# anemometer-r2.net
KiCad netlist of a schematic drawn in EAGLE
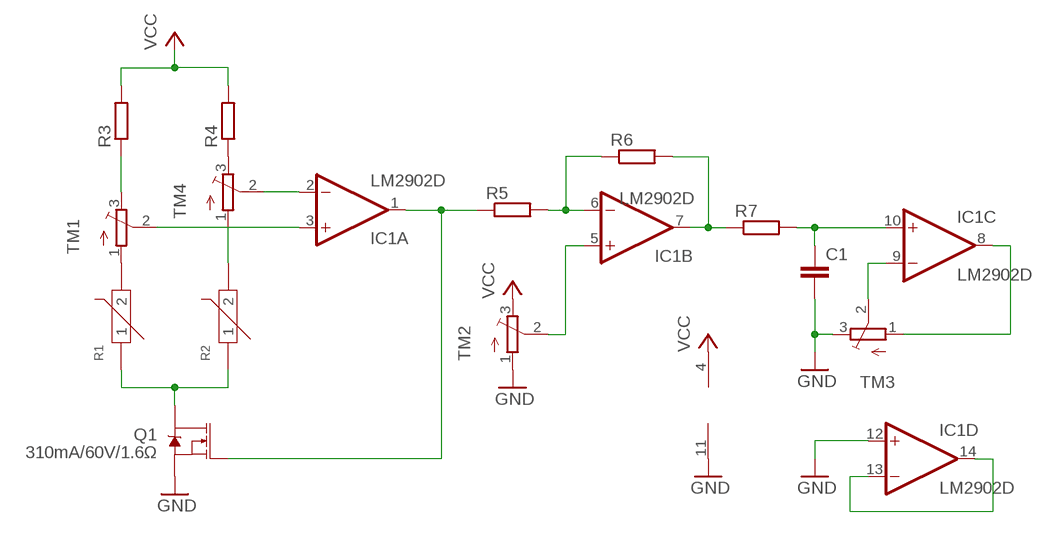
[diagram p0: schematic, sheet 1]

(export (version "E")
  (design (tool "Eeschema 10.0.6"))
  (components
    (comp (ref "C1")
      (value "C-EUC0603")
      (footprint "eagle-import:C0603")
      (libsource (lib "eagle-import") (part "C-EUC0603"))
    )
    (comp (ref "IC1")
      (value "LM2902D")
      (footprint "eagle-import:SO14")
      (fields (field (name "SPICEPREFIX") "J"))
      (libsource (lib "eagle-import") (part "LM2902D"))
    )
    (comp (ref "Q1")
      (value "310mA/60V/1.6Ω")
      (footprint "eagle-import:SOT323")
      (libsource (lib "eagle-import") (part "MOSFET-NCH-2N7002PW"))
    )
    (comp (ref "R1")
      (value "NCP18WF104F03RC")
      (footprint "eagle-import:R0603")
      (libsource (lib "eagle-import") (part "THERMISTOR-RES-NTC-100K(0603)"))
    )
    (comp (ref "R2")
      (value "NCP18WF104F03RC")
      (footprint "eagle-import:R0603")
      (libsource (lib "eagle-import") (part "THERMISTOR-RES-NTC-100K(0603)"))
    )
    (comp (ref "R3")
      (value "R-EU_R0603")
      (footprint "eagle-import:R0603")
      (libsource (lib "eagle-import") (part "R-EU_R0603"))
    )
    (comp (ref "R4")
      (value "R-EU_R0603")
      (footprint "eagle-import:R0603")
      (libsource (lib "eagle-import") (part "R-EU_R0603"))
    )
    (comp (ref "R5")
      (value "R-EU_R0603")
      (footprint "eagle-import:R0603")
      (libsource (lib "eagle-import") (part "R-EU_R0603"))
    )
    (comp (ref "R6")
      (value "R-EU_R0603")
      (footprint "eagle-import:R0603")
      (libsource (lib "eagle-import") (part "R-EU_R0603"))
    )
    (comp (ref "R7")
      (value "R-EU_R0603")
      (footprint "eagle-import:R0603")
      (libsource (lib "eagle-import") (part "R-EU_R0603"))
    )
    (comp (ref "TM1")
      (value "TRIMPOTTC33X")
      (footprint "eagle-import:TC33X")
      (libsource (lib "eagle-import") (part "TRIMPOTTC33X"))
    )
    (comp (ref "TM2")
      (value "TRIMPOTTC33X")
      (footprint "eagle-import:TC33X")
      (libsource (lib "eagle-import") (part "TRIMPOTTC33X"))
    )
    (comp (ref "TM3")
      (value "TRIMPOTTC33X")
      (footprint "eagle-import:TC33X")
      (libsource (lib "eagle-import") (part "TRIMPOTTC33X"))
    )
    (comp (ref "TM4")
      (value "TRIMPOTTC33X")
      (footprint "eagle-import:TC33X")
      (libsource (lib "eagle-import") (part "TRIMPOTTC33X"))
    )
  )
  (nets
    (net (code "1") (name "GND") (class "Default")
      (node (ref "C1") (pin "2") (pinfunction "2_2") (pintype "passive"))
      (node (ref "IC1") (pin "11") (pinfunction "V-_11") (pintype "power_in"))
      (node (ref "IC1") (pin "12") (pinfunction "+IN_12") (pintype "input"))
      (node (ref "Q1") (pin "2") (pinfunction "S_2") (pintype "bidirectional"))
      (node (ref "TM2") (pin "1") (pinfunction "A_1") (pintype "passive"))
      (node (ref "TM3") (pin "3") (pinfunction "E_3") (pintype "passive"))
    )
    (net (code "2") (name "Net-(IC1A-+IN)") (class "Default")
      (node (ref "IC1") (pin "3") (pinfunction "+IN_3") (pintype "input"))
      (node (ref "TM1") (pin "2") (pinfunction "S_2") (pintype "passive"))
    )
    (net (code "3") (name "Net-(IC1A--IN)") (class "Default")
      (node (ref "IC1") (pin "2") (pinfunction "-IN_2") (pintype "input"))
      (node (ref "TM4") (pin "2") (pinfunction "S_2") (pintype "passive"))
    )
    (net (code "4") (name "Net-(IC1A-OUT)") (class "Default")
      (node (ref "IC1") (pin "1") (pinfunction "OUT_1") (pintype "output"))
      (node (ref "Q1") (pin "1") (pinfunction "G_1") (pintype "bidirectional"))
      (node (ref "R5") (pin "1") (pinfunction "1_1") (pintype "passive"))
    )
    (net (code "5") (name "Net-(IC1B-+IN)") (class "Default")
      (node (ref "IC1") (pin "5") (pinfunction "+IN_5") (pintype "input"))
      (node (ref "TM2") (pin "2") (pinfunction "S_2") (pintype "passive"))
    )
    (net (code "6") (name "Net-(IC1B--IN)") (class "Default")
      (node (ref "IC1") (pin "6") (pinfunction "-IN_6") (pintype "input"))
      (node (ref "R5") (pin "2") (pinfunction "2_2") (pintype "passive"))
      (node (ref "R6") (pin "1") (pinfunction "1_1") (pintype "passive"))
    )
    (net (code "7") (name "Net-(IC1B-OUT)") (class "Default")
      (node (ref "IC1") (pin "7") (pinfunction "OUT_7") (pintype "output"))
      (node (ref "R6") (pin "2") (pinfunction "2_2") (pintype "passive"))
      (node (ref "R7") (pin "1") (pinfunction "1_1") (pintype "passive"))
    )
    (net (code "8") (name "Net-(IC1C-+IN)") (class "Default")
      (node (ref "C1") (pin "1") (pinfunction "1_1") (pintype "passive"))
      (node (ref "IC1") (pin "10") (pinfunction "+IN_10") (pintype "input"))
      (node (ref "R7") (pin "2") (pinfunction "2_2") (pintype "passive"))
    )
    (net (code "9") (name "Net-(IC1C--IN)") (class "Default")
      (node (ref "IC1") (pin "9") (pinfunction "-IN_9") (pintype "input"))
      (node (ref "TM3") (pin "2") (pinfunction "S_2") (pintype "passive"))
    )
    (net (code "10") (name "Net-(IC1C-OUT)") (class "Default")
      (node (ref "IC1") (pin "8") (pinfunction "OUT_8") (pintype "output"))
      (node (ref "TM3") (pin "1") (pinfunction "A_1") (pintype "passive"))
    )
    (net (code "11") (name "Net-(IC1D--IN)") (class "Default")
      (node (ref "IC1") (pin "13") (pinfunction "-IN_13") (pintype "input"))
      (node (ref "IC1") (pin "14") (pinfunction "OUT_14") (pintype "output"))
    )
    (net (code "12") (name "Net-(Q1-D)") (class "Default")
      (node (ref "Q1") (pin "3") (pinfunction "D_3") (pintype "bidirectional"))
      (node (ref "R1") (pin "1") (pinfunction "1_1") (pintype "bidirectional"))
      (node (ref "R2") (pin "1") (pinfunction "1_1") (pintype "bidirectional"))
    )
    (net (code "13") (name "Net-(TM1-A)") (class "Default")
      (node (ref "R1") (pin "2") (pinfunction "2_2") (pintype "bidirectional"))
      (node (ref "TM1") (pin "1") (pinfunction "A_1") (pintype "passive"))
    )
    (net (code "14") (name "Net-(TM1-E)") (class "Default")
      (node (ref "R3") (pin "1") (pinfunction "1_1") (pintype "passive"))
      (node (ref "TM1") (pin "3") (pinfunction "E_3") (pintype "passive"))
    )
    (net (code "15") (name "Net-(TM4-A)") (class "Default")
      (node (ref "R2") (pin "2") (pinfunction "2_2") (pintype "bidirectional"))
      (node (ref "TM4") (pin "1") (pinfunction "A_1") (pintype "passive"))
    )
    (net (code "16") (name "Net-(TM4-E)") (class "Default")
      (node (ref "R4") (pin "1") (pinfunction "1_1") (pintype "passive"))
      (node (ref "TM4") (pin "3") (pinfunction "E_3") (pintype "passive"))
    )
    (net (code "17") (name "VCC") (class "Default")
      (node (ref "IC1") (pin "4") (pinfunction "V+_4") (pintype "power_in"))
      (node (ref "R3") (pin "2") (pinfunction "2_2") (pintype "passive"))
      (node (ref "R4") (pin "2") (pinfunction "2_2") (pintype "passive"))
      (node (ref "TM2") (pin "3") (pinfunction "E_3") (pintype "passive"))
    )
  )
)
